# LEDStatusBoard.net
KiCad netlist of a schematic drawn in EAGLE
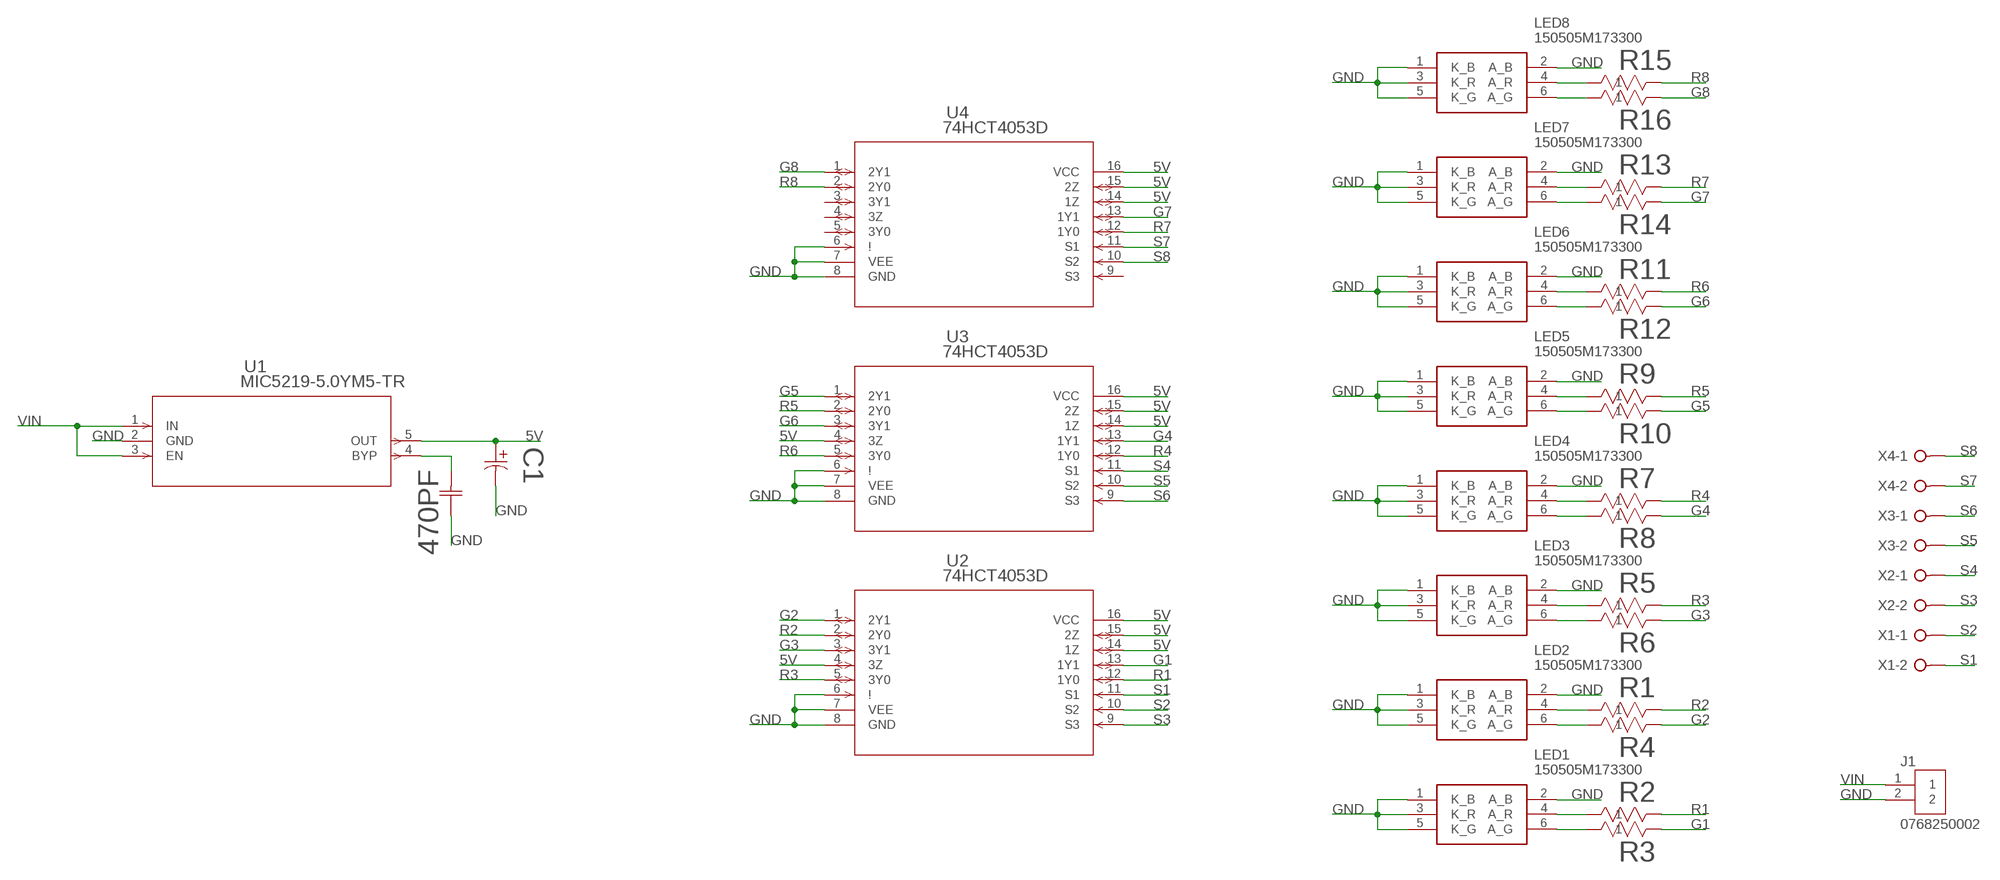
[diagram p0: schematic, sheet 1]

(export (version "E")
  (design (tool "Eeschema 10.0.6"))
  (components
    (comp (ref "470PF")
      (value "CGA1A2X7R1H471K030BA")
      (footprint "eagle-import:CAP_0603_TDK")
      (libsource (lib "eagle-import") (part "CGA1A2X7R1H471K030BA"))
    )
    (comp (ref "C1")
      (value "UWX1H2R2MCL1GB")
      (footprint "eagle-import:PCAP_4X5.4-ELECT_NCA")
      (libsource (lib "eagle-import") (part "UWX1H2R2MCL1GB"))
    )
    (comp (ref "J1")
      (value "0768250002")
      (footprint "eagle-import:MOLEX_0768250002")
      (fields (field (name "MF") "Molex"))
      (libsource (lib "eagle-import") (part "0768250002"))
    )
    (comp (ref "LED1")
      (value "150505M173300")
      (footprint "eagle-import:150505M173300")
      (fields (field (name "MOUSER_PART_NUMBER") "710-150505M173300"))
      (libsource (lib "eagle-import") (part "150505M173300"))
    )
    (comp (ref "LED2")
      (value "150505M173300")
      (footprint "eagle-import:150505M173300")
      (fields (field (name "MOUSER_PART_NUMBER") "710-150505M173300"))
      (libsource (lib "eagle-import") (part "150505M173300"))
    )
    (comp (ref "LED3")
      (value "150505M173300")
      (footprint "eagle-import:150505M173300")
      (fields (field (name "MOUSER_PART_NUMBER") "710-150505M173300"))
      (libsource (lib "eagle-import") (part "150505M173300"))
    )
    (comp (ref "LED4")
      (value "150505M173300")
      (footprint "eagle-import:150505M173300")
      (fields (field (name "MOUSER_PART_NUMBER") "710-150505M173300"))
      (libsource (lib "eagle-import") (part "150505M173300"))
    )
    (comp (ref "LED5")
      (value "150505M173300")
      (footprint "eagle-import:150505M173300")
      (fields (field (name "MOUSER_PART_NUMBER") "710-150505M173300"))
      (libsource (lib "eagle-import") (part "150505M173300"))
    )
    (comp (ref "LED6")
      (value "150505M173300")
      (footprint "eagle-import:150505M173300")
      (fields (field (name "MOUSER_PART_NUMBER") "710-150505M173300"))
      (libsource (lib "eagle-import") (part "150505M173300"))
    )
    (comp (ref "LED7")
      (value "150505M173300")
      (footprint "eagle-import:150505M173300")
      (fields (field (name "MOUSER_PART_NUMBER") "710-150505M173300"))
      (libsource (lib "eagle-import") (part "150505M173300"))
    )
    (comp (ref "LED8")
      (value "150505M173300")
      (footprint "eagle-import:150505M173300")
      (fields (field (name "MOUSER_PART_NUMBER") "710-150505M173300"))
      (libsource (lib "eagle-import") (part "150505M173300"))
    )
    (comp (ref "R1")
      (value "RMCF1206JT130R")
      (footprint "eagle-import:RES_RMCF1206_STP")
      (fields (field (name "COPYRIGHT") "Copyright (C) 2018 Accelerated Designs. All rights reserved"))
      (libsource (lib "eagle-import") (part "RMCF1206JT130R"))
    )
    (comp (ref "R2")
      (value "RMCF1206JT130R")
      (footprint "eagle-import:RES_RMCF1206_STP")
      (fields (field (name "COPYRIGHT") "Copyright (C) 2018 Accelerated Designs. All rights reserved"))
      (libsource (lib "eagle-import") (part "RMCF1206JT130R"))
    )
    (comp (ref "R3")
      (value "RMCF1206JT130R")
      (footprint "eagle-import:RES_RMCF1206_STP")
      (fields (field (name "COPYRIGHT") "Copyright (C) 2018 Accelerated Designs. All rights reserved"))
      (libsource (lib "eagle-import") (part "RMCF1206JT130R"))
    )
    (comp (ref "R4")
      (value "RMCF1206JT130R")
      (footprint "eagle-import:RES_RMCF1206_STP")
      (fields (field (name "COPYRIGHT") "Copyright (C) 2018 Accelerated Designs. All rights reserved"))
      (libsource (lib "eagle-import") (part "RMCF1206JT130R"))
    )
    (comp (ref "R5")
      (value "RMCF1206JT130R")
      (footprint "eagle-import:RES_RMCF1206_STP")
      (fields (field (name "COPYRIGHT") "Copyright (C) 2018 Accelerated Designs. All rights reserved"))
      (libsource (lib "eagle-import") (part "RMCF1206JT130R"))
    )
    (comp (ref "R6")
      (value "RMCF1206JT130R")
      (footprint "eagle-import:RES_RMCF1206_STP")
      (fields (field (name "COPYRIGHT") "Copyright (C) 2018 Accelerated Designs. All rights reserved"))
      (libsource (lib "eagle-import") (part "RMCF1206JT130R"))
    )
    (comp (ref "R7")
      (value "RMCF1206JT130R")
      (footprint "eagle-import:RES_RMCF1206_STP")
      (fields (field (name "COPYRIGHT") "Copyright (C) 2018 Accelerated Designs. All rights reserved"))
      (libsource (lib "eagle-import") (part "RMCF1206JT130R"))
    )
    (comp (ref "R8")
      (value "RMCF1206JT130R")
      (footprint "eagle-import:RES_RMCF1206_STP")
      (fields (field (name "COPYRIGHT") "Copyright (C) 2018 Accelerated Designs. All rights reserved"))
      (libsource (lib "eagle-import") (part "RMCF1206JT130R"))
    )
    (comp (ref "R9")
      (value "RMCF1206JT130R")
      (footprint "eagle-import:RES_RMCF1206_STP")
      (fields (field (name "COPYRIGHT") "Copyright (C) 2018 Accelerated Designs. All rights reserved"))
      (libsource (lib "eagle-import") (part "RMCF1206JT130R"))
    )
    (comp (ref "R10")
      (value "RMCF1206JT130R")
      (footprint "eagle-import:RES_RMCF1206_STP")
      (fields (field (name "COPYRIGHT") "Copyright (C) 2018 Accelerated Designs. All rights reserved"))
      (libsource (lib "eagle-import") (part "RMCF1206JT130R"))
    )
    (comp (ref "R11")
      (value "RMCF1206JT130R")
      (footprint "eagle-import:RES_RMCF1206_STP")
      (fields (field (name "COPYRIGHT") "Copyright (C) 2018 Accelerated Designs. All rights reserved"))
      (libsource (lib "eagle-import") (part "RMCF1206JT130R"))
    )
    (comp (ref "R12")
      (value "RMCF1206JT130R")
      (footprint "eagle-import:RES_RMCF1206_STP")
      (fields (field (name "COPYRIGHT") "Copyright (C) 2018 Accelerated Designs. All rights reserved"))
      (libsource (lib "eagle-import") (part "RMCF1206JT130R"))
    )
    (comp (ref "R13")
      (value "RMCF1206JT130R")
      (footprint "eagle-import:RES_RMCF1206_STP")
      (fields (field (name "COPYRIGHT") "Copyright (C) 2018 Accelerated Designs. All rights reserved"))
      (libsource (lib "eagle-import") (part "RMCF1206JT130R"))
    )
    (comp (ref "R14")
      (value "RMCF1206JT130R")
      (footprint "eagle-import:RES_RMCF1206_STP")
      (fields (field (name "COPYRIGHT") "Copyright (C) 2018 Accelerated Designs. All rights reserved"))
      (libsource (lib "eagle-import") (part "RMCF1206JT130R"))
    )
    (comp (ref "R15")
      (value "RMCF1206JT130R")
      (footprint "eagle-import:RES_RMCF1206_STP")
      (fields (field (name "COPYRIGHT") "Copyright (C) 2018 Accelerated Designs. All rights reserved"))
      (libsource (lib "eagle-import") (part "RMCF1206JT130R"))
    )
    (comp (ref "R16")
      (value "RMCF1206JT130R")
      (footprint "eagle-import:RES_RMCF1206_STP")
      (fields (field (name "COPYRIGHT") "Copyright (C) 2018 Accelerated Designs. All rights reserved"))
      (libsource (lib "eagle-import") (part "RMCF1206JT130R"))
    )
    (comp (ref "U1")
      (value "MIC5219-5.0YM5-TR")
      (footprint "eagle-import:SOT-23-5_M5_MCH")
      (fields (field (name "COPYRIGHT") "Copyright (C) 2018 Accelerated Designs. All rights reserved"))
      (libsource (lib "eagle-import") (part "MIC5219-5.0YM5-TR"))
    )
    (comp (ref "U2")
      (value "74HCT4053D")
      (footprint "eagle-import:SOT109-1_NXP")
      (libsource (lib "eagle-import") (part "74HCT4053D"))
    )
    (comp (ref "U3")
      (value "74HCT4053D")
      (footprint "eagle-import:SOT109-1_NXP")
      (libsource (lib "eagle-import") (part "74HCT4053D"))
    )
    (comp (ref "U4")
      (value "74HCT4053D")
      (footprint "eagle-import:SOT109-1_NXP")
      (libsource (lib "eagle-import") (part "74HCT4053D"))
    )
    (comp (ref "X1")
      (value "W237-02P")
      (footprint "eagle-import:W237-132")
      (libsource (lib "eagle-import") (part "W237-02P"))
    )
    (comp (ref "X2")
      (value "W237-02P")
      (footprint "eagle-import:W237-132")
      (libsource (lib "eagle-import") (part "W237-02P"))
    )
    (comp (ref "X3")
      (value "W237-02P")
      (footprint "eagle-import:W237-132")
      (libsource (lib "eagle-import") (part "W237-02P"))
    )
    (comp (ref "X4")
      (value "W237-02P")
      (footprint "eagle-import:W237-132")
      (libsource (lib "eagle-import") (part "W237-02P"))
    )
  )
  (nets
    (net (code "1") (name "/5V") (class "Default")
      (node (ref "C1") (pin "1") (pinfunction "1_1") (pintype "passive"))
      (node (ref "U1") (pin "5") (pinfunction "OUT_5") (pintype "output"))
      (node (ref "U2") (pin "14") (pinfunction "1Z_14") (pintype "bidirectional"))
      (node (ref "U2") (pin "15") (pinfunction "2Z_15") (pintype "bidirectional"))
      (node (ref "U2") (pin "16") (pinfunction "VCC_16") (pintype "power_in"))
      (node (ref "U2") (pin "4") (pinfunction "3Z_4") (pintype "bidirectional"))
      (node (ref "U3") (pin "14") (pinfunction "1Z_14") (pintype "bidirectional"))
      (node (ref "U3") (pin "15") (pinfunction "2Z_15") (pintype "bidirectional"))
      (node (ref "U3") (pin "16") (pinfunction "VCC_16") (pintype "power_in"))
      (node (ref "U3") (pin "4") (pinfunction "3Z_4") (pintype "bidirectional"))
      (node (ref "U4") (pin "14") (pinfunction "1Z_14") (pintype "bidirectional"))
      (node (ref "U4") (pin "15") (pinfunction "2Z_15") (pintype "bidirectional"))
      (node (ref "U4") (pin "16") (pinfunction "VCC_16") (pintype "power_in"))
    )
    (net (code "2") (name "/G1") (class "Default")
      (node (ref "R3") (pin "2") (pinfunction "2_2") (pintype "passive"))
      (node (ref "U2") (pin "13") (pinfunction "1Y1_13") (pintype "bidirectional"))
    )
    (net (code "3") (name "/G2") (class "Default")
      (node (ref "R4") (pin "2") (pinfunction "2_2") (pintype "passive"))
      (node (ref "U2") (pin "1") (pinfunction "2Y1_1") (pintype "bidirectional"))
    )
    (net (code "4") (name "/G3") (class "Default")
      (node (ref "R6") (pin "2") (pinfunction "2_2") (pintype "passive"))
      (node (ref "U2") (pin "3") (pinfunction "3Y1_3") (pintype "bidirectional"))
    )
    (net (code "5") (name "/G4") (class "Default")
      (node (ref "R8") (pin "2") (pinfunction "2_2") (pintype "passive"))
      (node (ref "U3") (pin "13") (pinfunction "1Y1_13") (pintype "bidirectional"))
    )
    (net (code "6") (name "/G5") (class "Default")
      (node (ref "R10") (pin "2") (pinfunction "2_2") (pintype "passive"))
      (node (ref "U3") (pin "1") (pinfunction "2Y1_1") (pintype "bidirectional"))
    )
    (net (code "7") (name "/G6") (class "Default")
      (node (ref "R12") (pin "2") (pinfunction "2_2") (pintype "passive"))
      (node (ref "U3") (pin "3") (pinfunction "3Y1_3") (pintype "bidirectional"))
    )
    (net (code "8") (name "/G7") (class "Default")
      (node (ref "R14") (pin "2") (pinfunction "2_2") (pintype "passive"))
      (node (ref "U4") (pin "13") (pinfunction "1Y1_13") (pintype "bidirectional"))
    )
    (net (code "9") (name "/G8") (class "Default")
      (node (ref "R16") (pin "2") (pinfunction "2_2") (pintype "passive"))
      (node (ref "U4") (pin "1") (pinfunction "2Y1_1") (pintype "bidirectional"))
    )
    (net (code "10") (name "/GND") (class "Default")
      (node (ref "470PF") (pin "1") (pinfunction "1_1") (pintype "passive"))
      (node (ref "C1") (pin "2") (pinfunction "2_2") (pintype "passive"))
      (node (ref "J1") (pin "2") (pinfunction "2_2") (pintype "passive"))
      (node (ref "LED1") (pin "1") (pinfunction "K_B_1") (pintype "bidirectional"))
      (node (ref "LED1") (pin "2") (pinfunction "A_B_2") (pintype "bidirectional"))
      (node (ref "LED1") (pin "3") (pinfunction "K_R_3") (pintype "bidirectional"))
      (node (ref "LED1") (pin "5") (pinfunction "K_G_5") (pintype "bidirectional"))
      (node (ref "LED2") (pin "1") (pinfunction "K_B_1") (pintype "bidirectional"))
      (node (ref "LED2") (pin "2") (pinfunction "A_B_2") (pintype "bidirectional"))
      (node (ref "LED2") (pin "3") (pinfunction "K_R_3") (pintype "bidirectional"))
      (node (ref "LED2") (pin "5") (pinfunction "K_G_5") (pintype "bidirectional"))
      (node (ref "LED3") (pin "1") (pinfunction "K_B_1") (pintype "bidirectional"))
      (node (ref "LED3") (pin "2") (pinfunction "A_B_2") (pintype "bidirectional"))
      (node (ref "LED3") (pin "3") (pinfunction "K_R_3") (pintype "bidirectional"))
      (node (ref "LED3") (pin "5") (pinfunction "K_G_5") (pintype "bidirectional"))
      (node (ref "LED4") (pin "1") (pinfunction "K_B_1") (pintype "bidirectional"))
      (node (ref "LED4") (pin "2") (pinfunction "A_B_2") (pintype "bidirectional"))
      (node (ref "LED4") (pin "3") (pinfunction "K_R_3") (pintype "bidirectional"))
      (node (ref "LED4") (pin "5") (pinfunction "K_G_5") (pintype "bidirectional"))
      (node (ref "LED5") (pin "1") (pinfunction "K_B_1") (pintype "bidirectional"))
      (node (ref "LED5") (pin "2") (pinfunction "A_B_2") (pintype "bidirectional"))
      (node (ref "LED5") (pin "3") (pinfunction "K_R_3") (pintype "bidirectional"))
      (node (ref "LED5") (pin "5") (pinfunction "K_G_5") (pintype "bidirectional"))
      (node (ref "LED6") (pin "1") (pinfunction "K_B_1") (pintype "bidirectional"))
      (node (ref "LED6") (pin "2") (pinfunction "A_B_2") (pintype "bidirectional"))
      (node (ref "LED6") (pin "3") (pinfunction "K_R_3") (pintype "bidirectional"))
      (node (ref "LED6") (pin "5") (pinfunction "K_G_5") (pintype "bidirectional"))
      (node (ref "LED7") (pin "1") (pinfunction "K_B_1") (pintype "bidirectional"))
      (node (ref "LED7") (pin "2") (pinfunction "A_B_2") (pintype "bidirectional"))
      (node (ref "LED7") (pin "3") (pinfunction "K_R_3") (pintype "bidirectional"))
      (node (ref "LED7") (pin "5") (pinfunction "K_G_5") (pintype "bidirectional"))
      (node (ref "LED8") (pin "1") (pinfunction "K_B_1") (pintype "bidirectional"))
      (node (ref "LED8") (pin "2") (pinfunction "A_B_2") (pintype "bidirectional"))
      (node (ref "LED8") (pin "3") (pinfunction "K_R_3") (pintype "bidirectional"))
      (node (ref "LED8") (pin "5") (pinfunction "K_G_5") (pintype "bidirectional"))
      (node (ref "U1") (pin "2") (pinfunction "GND_2") (pintype "power_in"))
      (node (ref "U2") (pin "6") (pinfunction "~_6") (pintype "input"))
      (node (ref "U2") (pin "7") (pinfunction "VEE_7") (pintype "power_in"))
      (node (ref "U2") (pin "8") (pinfunction "GND_8") (pintype "power_in"))
      (node (ref "U3") (pin "6") (pinfunction "~_6") (pintype "input"))
      (node (ref "U3") (pin "7") (pinfunction "VEE_7") (pintype "power_in"))
      (node (ref "U3") (pin "8") (pinfunction "GND_8") (pintype "power_in"))
      (node (ref "U4") (pin "6") (pinfunction "~_6") (pintype "input"))
      (node (ref "U4") (pin "7") (pinfunction "VEE_7") (pintype "power_in"))
      (node (ref "U4") (pin "8") (pinfunction "GND_8") (pintype "power_in"))
    )
    (net (code "11") (name "/R1") (class "Default")
      (node (ref "R2") (pin "2") (pinfunction "2_2") (pintype "passive"))
      (node (ref "U2") (pin "12") (pinfunction "1Y0_12") (pintype "bidirectional"))
    )
    (net (code "12") (name "/R2") (class "Default")
      (node (ref "R1") (pin "2") (pinfunction "2_2") (pintype "passive"))
      (node (ref "U2") (pin "2") (pinfunction "2Y0_2") (pintype "bidirectional"))
    )
    (net (code "13") (name "/R3") (class "Default")
      (node (ref "R5") (pin "2") (pinfunction "2_2") (pintype "passive"))
      (node (ref "U2") (pin "5") (pinfunction "3Y0_5") (pintype "bidirectional"))
    )
    (net (code "14") (name "/R4") (class "Default")
      (node (ref "R7") (pin "2") (pinfunction "2_2") (pintype "passive"))
      (node (ref "U3") (pin "12") (pinfunction "1Y0_12") (pintype "bidirectional"))
    )
    (net (code "15") (name "/R5") (class "Default")
      (node (ref "R9") (pin "2") (pinfunction "2_2") (pintype "passive"))
      (node (ref "U3") (pin "2") (pinfunction "2Y0_2") (pintype "bidirectional"))
    )
    (net (code "16") (name "/R6") (class "Default")
      (node (ref "R11") (pin "2") (pinfunction "2_2") (pintype "passive"))
      (node (ref "U3") (pin "5") (pinfunction "3Y0_5") (pintype "bidirectional"))
    )
    (net (code "17") (name "/R7") (class "Default")
      (node (ref "R13") (pin "2") (pinfunction "2_2") (pintype "passive"))
      (node (ref "U4") (pin "12") (pinfunction "1Y0_12") (pintype "bidirectional"))
    )
    (net (code "18") (name "/R8") (class "Default")
      (node (ref "R15") (pin "2") (pinfunction "2_2") (pintype "passive"))
      (node (ref "U4") (pin "2") (pinfunction "2Y0_2") (pintype "bidirectional"))
    )
    (net (code "19") (name "/S1") (class "Default")
      (node (ref "U2") (pin "11") (pinfunction "S1_11") (pintype "input"))
      (node (ref "X1") (pin "2") (pinfunction "KL_2") (pintype "passive"))
    )
    (net (code "20") (name "/S2") (class "Default")
      (node (ref "U2") (pin "10") (pinfunction "S2_10") (pintype "input"))
      (node (ref "X1") (pin "1") (pinfunction "KL_1") (pintype "passive"))
    )
    (net (code "21") (name "/S3") (class "Default")
      (node (ref "U2") (pin "9") (pinfunction "S3_9") (pintype "input"))
      (node (ref "X2") (pin "2") (pinfunction "KL_2") (pintype "passive"))
    )
    (net (code "22") (name "/S4") (class "Default")
      (node (ref "U3") (pin "11") (pinfunction "S1_11") (pintype "input"))
      (node (ref "X2") (pin "1") (pinfunction "KL_1") (pintype "passive"))
    )
    (net (code "23") (name "/S5") (class "Default")
      (node (ref "U3") (pin "10") (pinfunction "S2_10") (pintype "input"))
      (node (ref "X3") (pin "2") (pinfunction "KL_2") (pintype "passive"))
    )
    (net (code "24") (name "/S6") (class "Default")
      (node (ref "U3") (pin "9") (pinfunction "S3_9") (pintype "input"))
      (node (ref "X3") (pin "1") (pinfunction "KL_1") (pintype "passive"))
    )
    (net (code "25") (name "/S7") (class "Default")
      (node (ref "U4") (pin "11") (pinfunction "S1_11") (pintype "input"))
      (node (ref "X4") (pin "2") (pinfunction "KL_2") (pintype "passive"))
    )
    (net (code "26") (name "/S8") (class "Default")
      (node (ref "U4") (pin "10") (pinfunction "S2_10") (pintype "input"))
      (node (ref "X4") (pin "1") (pinfunction "KL_1") (pintype "passive"))
    )
    (net (code "27") (name "/VIN") (class "Default")
      (node (ref "J1") (pin "1") (pinfunction "1_1") (pintype "passive"))
      (node (ref "U1") (pin "1") (pinfunction "IN_1") (pintype "input"))
      (node (ref "U1") (pin "3") (pinfunction "EN_3") (pintype "input"))
    )
    (net (code "28") (name "Net-(LED1-A_G)") (class "Default")
      (node (ref "LED1") (pin "6") (pinfunction "A_G_6") (pintype "bidirectional"))
      (node (ref "R3") (pin "1") (pinfunction "1_1") (pintype "passive"))
    )
    (net (code "29") (name "Net-(LED1-A_R)") (class "Default")
      (node (ref "LED1") (pin "4") (pinfunction "A_R_4") (pintype "bidirectional"))
      (node (ref "R2") (pin "1") (pinfunction "1_1") (pintype "passive"))
    )
    (net (code "30") (name "Net-(LED2-A_G)") (class "Default")
      (node (ref "LED2") (pin "6") (pinfunction "A_G_6") (pintype "bidirectional"))
      (node (ref "R4") (pin "1") (pinfunction "1_1") (pintype "passive"))
    )
    (net (code "31") (name "Net-(LED2-A_R)") (class "Default")
      (node (ref "LED2") (pin "4") (pinfunction "A_R_4") (pintype "bidirectional"))
      (node (ref "R1") (pin "1") (pinfunction "1_1") (pintype "passive"))
    )
    (net (code "32") (name "Net-(LED3-A_G)") (class "Default")
      (node (ref "LED3") (pin "6") (pinfunction "A_G_6") (pintype "bidirectional"))
      (node (ref "R6") (pin "1") (pinfunction "1_1") (pintype "passive"))
    )
    (net (code "33") (name "Net-(LED3-A_R)") (class "Default")
      (node (ref "LED3") (pin "4") (pinfunction "A_R_4") (pintype "bidirectional"))
      (node (ref "R5") (pin "1") (pinfunction "1_1") (pintype "passive"))
    )
    (net (code "34") (name "Net-(LED4-A_G)") (class "Default")
      (node (ref "LED4") (pin "6") (pinfunction "A_G_6") (pintype "bidirectional"))
      (node (ref "R8") (pin "1") (pinfunction "1_1") (pintype "passive"))
    )
    (net (code "35") (name "Net-(LED4-A_R)") (class "Default")
      (node (ref "LED4") (pin "4") (pinfunction "A_R_4") (pintype "bidirectional"))
      (node (ref "R7") (pin "1") (pinfunction "1_1") (pintype "passive"))
    )
    (net (code "36") (name "Net-(LED5-A_G)") (class "Default")
      (node (ref "LED5") (pin "6") (pinfunction "A_G_6") (pintype "bidirectional"))
      (node (ref "R10") (pin "1") (pinfunction "1_1") (pintype "passive"))
    )
    (net (code "37") (name "Net-(LED5-A_R)") (class "Default")
      (node (ref "LED5") (pin "4") (pinfunction "A_R_4") (pintype "bidirectional"))
      (node (ref "R9") (pin "1") (pinfunction "1_1") (pintype "passive"))
    )
    (net (code "38") (name "Net-(LED6-A_G)") (class "Default")
      (node (ref "LED6") (pin "6") (pinfunction "A_G_6") (pintype "bidirectional"))
      (node (ref "R12") (pin "1") (pinfunction "1_1") (pintype "passive"))
    )
    (net (code "39") (name "Net-(LED6-A_R)") (class "Default")
      (node (ref "LED6") (pin "4") (pinfunction "A_R_4") (pintype "bidirectional"))
      (node (ref "R11") (pin "1") (pinfunction "1_1") (pintype "passive"))
    )
    (net (code "40") (name "Net-(LED7-A_G)") (class "Default")
      (node (ref "LED7") (pin "6") (pinfunction "A_G_6") (pintype "bidirectional"))
      (node (ref "R14") (pin "1") (pinfunction "1_1") (pintype "passive"))
    )
    (net (code "41") (name "Net-(LED7-A_R)") (class "Default")
      (node (ref "LED7") (pin "4") (pinfunction "A_R_4") (pintype "bidirectional"))
      (node (ref "R13") (pin "1") (pinfunction "1_1") (pintype "passive"))
    )
    (net (code "42") (name "Net-(LED8-A_G)") (class "Default")
      (node (ref "LED8") (pin "6") (pinfunction "A_G_6") (pintype "bidirectional"))
      (node (ref "R16") (pin "1") (pinfunction "1_1") (pintype "passive"))
    )
    (net (code "43") (name "Net-(LED8-A_R)") (class "Default")
      (node (ref "LED8") (pin "4") (pinfunction "A_R_4") (pintype "bidirectional"))
      (node (ref "R15") (pin "1") (pinfunction "1_1") (pintype "passive"))
    )
    (net (code "44") (name "Net-(U1-BYP)") (class "Default")
      (node (ref "470PF") (pin "2") (pinfunction "2_2") (pintype "passive"))
      (node (ref "U1") (pin "4") (pinfunction "BYP_4") (pintype "output"))
    )
    (net (code "45") (name "unconnected-(U4-3Y0-Pad5)") (class "Default")
      (node (ref "U4") (pin "5") (pinfunction "3Y0_5") (pintype "bidirectional"))
    )
    (net (code "46") (name "unconnected-(U4-3Y1-Pad3)") (class "Default")
      (node (ref "U4") (pin "3") (pinfunction "3Y1_3") (pintype "bidirectional"))
    )
    (net (code "47") (name "unconnected-(U4-3Z-Pad4)") (class "Default")
      (node (ref "U4") (pin "4") (pinfunction "3Z_4") (pintype "bidirectional"))
    )
    (net (code "48") (name "unconnected-(U4-S3-Pad9)") (class "Default")
      (node (ref "U4") (pin "9") (pinfunction "S3_9") (pintype "input"))
    )
  )
)
